# 180V_StepUp.net
KiCad netlist of a schematic drawn in EAGLE
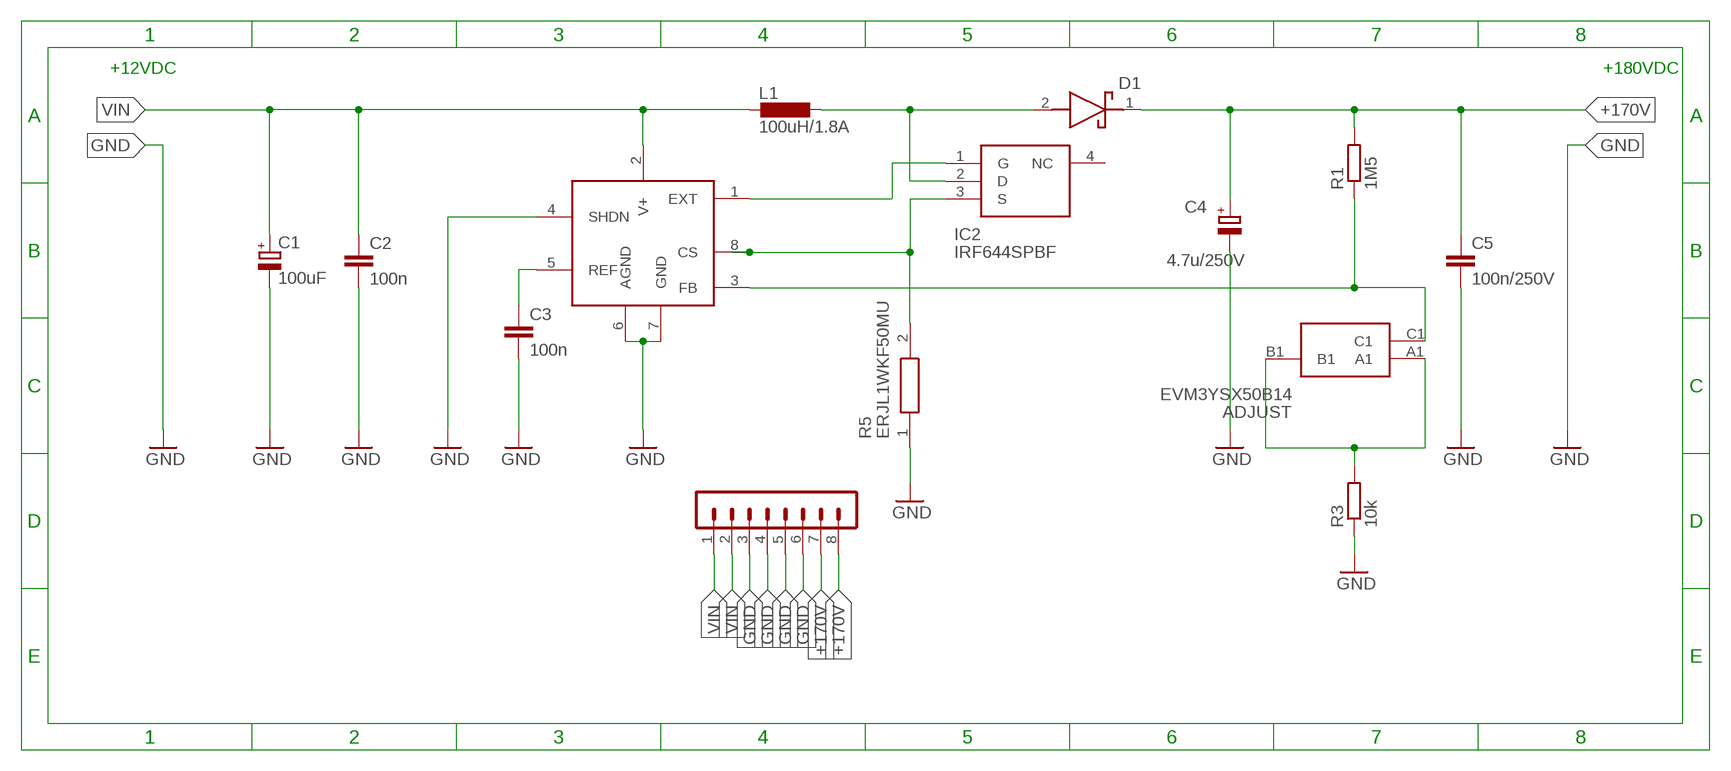
[diagram p0: schematic, sheet 1]
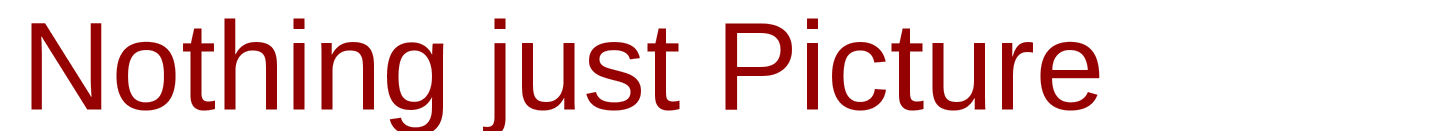
[diagram p1: schematic, sheet 2]

(export (version "E")
  (design (tool "Eeschema 10.0.6"))
  (components
    (comp (ref "ADJUST")
      (value "EVM3YSX50B14")
      (footprint "eagle-import:EVM3YSX50B14")
      (libsource (lib "eagle-import") (part "EVM3YSX50B14"))
    )
    (comp (ref "C1")
      (value "100uF")
      (footprint "eagle-import:E2-4")
      (libsource (lib "eagle-import") (part "CPOL-EUE2-4"))
    )
    (comp (ref "C2")
      (value "100n")
      (footprint "eagle-import:C0805")
      (libsource (lib "eagle-import") (part "C-EUC0805"))
    )
    (comp (ref "C3")
      (value "100n")
      (footprint "eagle-import:C0805")
      (libsource (lib "eagle-import") (part "C-EUC0805"))
    )
    (comp (ref "C4")
      (value "4.7u/250V")
      (footprint "eagle-import:E2,5-7")
      (libsource (lib "eagle-import") (part "CPOL-EUE2.5-7"))
    )
    (comp (ref "C5")
      (value "100n/250V")
      (footprint "eagle-import:C2225K")
      (libsource (lib "eagle-import") (part "C-EUC2225K"))
    )
    (comp (ref "D1")
      (value "LSM115JE3_TR13")
      (footprint "eagle-import:DIOM5436X330N")
      (fields
        (field (name "MANUFACTURER_PART_NUMBER") "LSM115JE3/TR13")
        (field (name "MOUSER_PART_NUMBER") "494-LSM115JE3/TR13")
      )
      (libsource (lib "eagle-import") (part "LSM115JE3_TR13"))
    )
    (comp (ref "IC1")
      (value "MAX1771")
      (footprint "eagle-import:SO08")
      (libsource (lib "eagle-import") (part "MAX1771"))
    )
    (comp (ref "IC2")
      (value "IRF644SPBF")
      (footprint "eagle-import:TO254P1524X483-4N")
      (fields (field (name "MOUSER_PART_NUMBER") "844-IRF644SPBF"))
      (libsource (lib "eagle-import") (part "IRF644SPBF"))
    )
    (comp (ref "L1")
      (value "100uH/1.8A")
      (footprint "eagle-import:DO3316P")
      (libsource (lib "eagle-import") (part "DO3316P"))
    )
    (comp (ref "R1")
      (value "1M5")
      (footprint "eagle-import:R0805")
      (libsource (lib "eagle-import") (part "R-EU_R0805"))
    )
    (comp (ref "R3")
      (value "10k")
      (footprint "eagle-import:R0805")
      (libsource (lib "eagle-import") (part "R-EU_R0805"))
    )
    (comp (ref "R5")
      (value "ERJL1WKF50MU")
      (footprint "eagle-import:RESC6432X120N")
      (libsource (lib "eagle-import") (part "ERJL1WKF50MU"))
    )
    (comp (ref "SV1")
      (value "PINHEADER-1X8")
      (footprint "eagle-import:MA08-1")
      (libsource (lib "eagle-import") (part "PINHEADER-1X8"))
    )
  )
  (nets
    (net (code "1") (name "+170V") (class "Default")
      (node (ref "C4") (pin "+") (pinfunction "+_+") (pintype "passive"))
      (node (ref "C5") (pin "1") (pinfunction "1_1") (pintype "passive"))
      (node (ref "D1") (pin "1") (pinfunction "K_1") (pintype "bidirectional"))
      (node (ref "R1") (pin "2") (pinfunction "2_2") (pintype "passive"))
      (node (ref "SV1") (pin "7") (pinfunction "7_7") (pintype "passive"))
      (node (ref "SV1") (pin "8") (pinfunction "8_8") (pintype "passive"))
    )
    (net (code "2") (name "GND") (class "Default")
      (node (ref "C1") (pin "-") (pinfunction "-_-") (pintype "passive"))
      (node (ref "C2") (pin "2") (pinfunction "2_2") (pintype "passive"))
      (node (ref "C3") (pin "2") (pinfunction "2_2") (pintype "passive"))
      (node (ref "C4") (pin "-") (pinfunction "-_-") (pintype "passive"))
      (node (ref "C5") (pin "2") (pinfunction "2_2") (pintype "passive"))
      (node (ref "IC1") (pin "4") (pinfunction "SHDN_4") (pintype "bidirectional"))
      (node (ref "IC1") (pin "6") (pinfunction "AGND_6") (pintype "bidirectional"))
      (node (ref "IC1") (pin "7") (pinfunction "GND_7") (pintype "bidirectional"))
      (node (ref "R3") (pin "1") (pinfunction "1_1") (pintype "passive"))
      (node (ref "R5") (pin "1") (pinfunction "1_1") (pintype "bidirectional"))
      (node (ref "SV1") (pin "3") (pinfunction "3_3") (pintype "passive"))
      (node (ref "SV1") (pin "4") (pinfunction "4_4") (pintype "passive"))
      (node (ref "SV1") (pin "5") (pinfunction "5_5") (pintype "passive"))
      (node (ref "SV1") (pin "6") (pinfunction "6_6") (pintype "passive"))
    )
    (net (code "3") (name "Net-(ADJUST-PadA1)") (class "Default")
      (node (ref "ADJUST") (pin "A1") (pinfunction "A1_A1") (pintype "bidirectional"))
      (node (ref "ADJUST") (pin "B1") (pinfunction "B1_B1") (pintype "bidirectional"))
      (node (ref "R3") (pin "2") (pinfunction "2_2") (pintype "passive"))
    )
    (net (code "4") (name "Net-(D1-A)") (class "Default")
      (node (ref "D1") (pin "2") (pinfunction "A_2") (pintype "bidirectional"))
      (node (ref "IC2") (pin "2") (pinfunction "D_2") (pintype "bidirectional"))
      (node (ref "L1") (pin "2") (pinfunction "2_2") (pintype "passive"))
    )
    (net (code "5") (name "Net-(IC1-CS)") (class "Default")
      (node (ref "IC1") (pin "8") (pinfunction "CS_8") (pintype "bidirectional"))
      (node (ref "IC2") (pin "3") (pinfunction "S_3") (pintype "bidirectional"))
      (node (ref "R5") (pin "2") (pinfunction "2_2") (pintype "bidirectional"))
    )
    (net (code "6") (name "Net-(IC1-EXT)") (class "Default")
      (node (ref "IC1") (pin "1") (pinfunction "EXT_1") (pintype "bidirectional"))
      (node (ref "IC2") (pin "1") (pinfunction "G_1") (pintype "bidirectional"))
    )
    (net (code "7") (name "Net-(IC1-FB)") (class "Default")
      (node (ref "ADJUST") (pin "C1") (pinfunction "C1_C1") (pintype "bidirectional"))
      (node (ref "IC1") (pin "3") (pinfunction "FB_3") (pintype "bidirectional"))
      (node (ref "R1") (pin "1") (pinfunction "1_1") (pintype "passive"))
    )
    (net (code "8") (name "Net-(IC1-REF)") (class "Default")
      (node (ref "C3") (pin "1") (pinfunction "1_1") (pintype "passive"))
      (node (ref "IC1") (pin "5") (pinfunction "REF_5") (pintype "bidirectional"))
    )
    (net (code "9") (name "VIN") (class "Default")
      (node (ref "C1") (pin "+") (pinfunction "+_+") (pintype "passive"))
      (node (ref "C2") (pin "1") (pinfunction "1_1") (pintype "passive"))
      (node (ref "IC1") (pin "2") (pinfunction "V+_2") (pintype "bidirectional"))
      (node (ref "L1") (pin "1") (pinfunction "1_1") (pintype "passive"))
      (node (ref "SV1") (pin "1") (pinfunction "1_1") (pintype "passive"))
      (node (ref "SV1") (pin "2") (pinfunction "2_2") (pintype "passive"))
    )
    (net (code "10") (name "unconnected-(IC2-NC-Pad4)") (class "Default")
      (node (ref "IC2") (pin "4") (pinfunction "NC_4") (pintype "no_connect"))
    )
  )
)
